# 4_ZynTra-Zynq-PS.net
KiCad netlist of a schematic drawn in Altium Designer
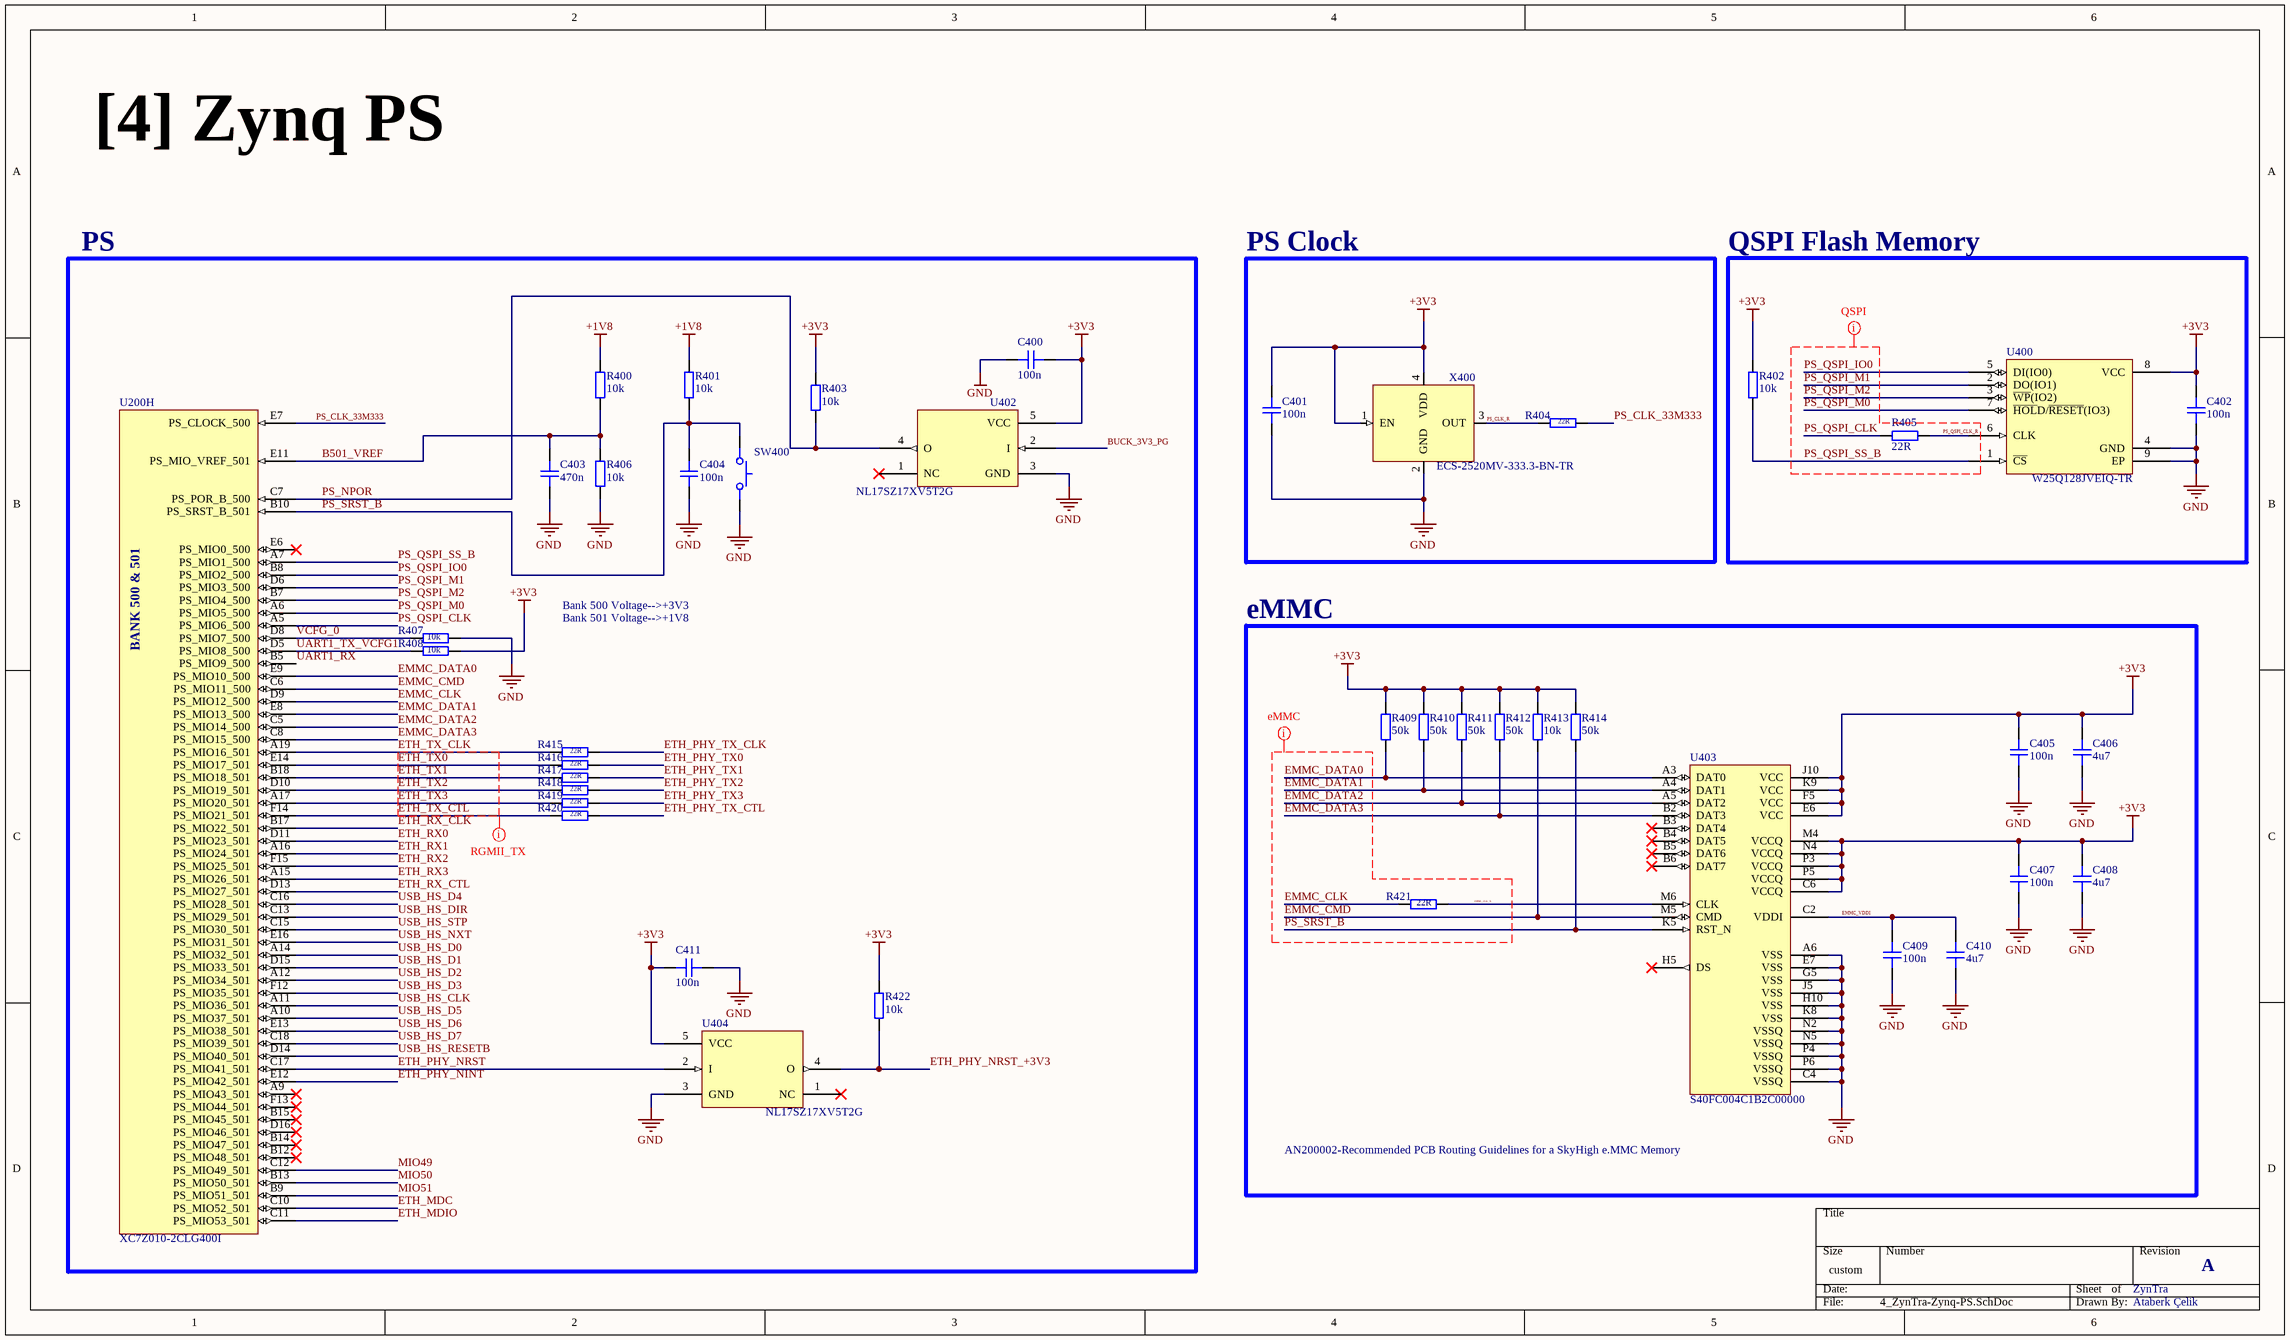
[diagram p0: 4_ZynTra-Zynq-PS.SchDoc]

(export (version "E")
  (design (tool "Eeschema 10.0.6"))
  (components
    (comp (ref "C400")
      (value "100n")
      (footprint "CAP_0201")
      (description "Capacitor SMD 0201")
      (libsource (lib "Schematic-Lib-PhilsLab") (part "CAP_0201"))
    )
    (comp (ref "C401")
      (value "100n")
      (footprint "CAP_0201")
      (description "Capacitor SMD 0201")
      (libsource (lib "Schematic-Lib-PhilsLab") (part "CAP_0201"))
    )
    (comp (ref "C402")
      (value "100n")
      (footprint "CAP_0201")
      (description "Capacitor SMD 0201")
      (libsource (lib "Schematic-Lib-PhilsLab") (part "CAP_0201"))
    )
    (comp (ref "C403")
      (value "470n")
      (footprint "CAP_0201")
      (description "Capacitor SMD 0201")
      (libsource (lib "Schematic-Lib-PhilsLab") (part "CAP_0201"))
    )
    (comp (ref "C404")
      (value "100n")
      (footprint "CAP_0201")
      (description "Capacitor SMD 0201")
      (libsource (lib "Schematic-Lib-PhilsLab") (part "CAP_0201"))
    )
    (comp (ref "C405")
      (value "100n")
      (footprint "CAP_0201")
      (description "Capacitor SMD 0201")
      (libsource (lib "Schematic-Lib-PhilsLab") (part "CAP_0201"))
    )
    (comp (ref "C406")
      (value "4u7")
      (footprint "CAP_0402")
      (description "Capacitor SMD 0402")
      (libsource (lib "Schematic-Lib-PhilsLab") (part "CAP_0402"))
    )
    (comp (ref "C407")
      (value "100n")
      (footprint "CAP_0201")
      (description "Capacitor SMD 0201")
      (libsource (lib "Schematic-Lib-PhilsLab") (part "CAP_0201"))
    )
    (comp (ref "C408")
      (value "4u7")
      (footprint "CAP_0402")
      (description "Capacitor SMD 0402")
      (libsource (lib "Schematic-Lib-PhilsLab") (part "CAP_0402"))
    )
    (comp (ref "C409")
      (value "100n")
      (footprint "CAP_0201")
      (description "Capacitor SMD 0201")
      (libsource (lib "Schematic-Lib-PhilsLab") (part "CAP_0201"))
    )
    (comp (ref "C410")
      (value "4u7")
      (footprint "CAP_0402")
      (description "Capacitor SMD 0402")
      (libsource (lib "Schematic-Lib-PhilsLab") (part "CAP_0402"))
    )
    (comp (ref "C411")
      (value "100n")
      (footprint "CAP_0201")
      (description "Capacitor SMD 0201")
      (libsource (lib "Schematic-Lib-PhilsLab") (part "CAP_0201"))
    )
    (comp (ref "R400")
      (value "10k")
      (footprint "RES_0402")
      (description "Resistor SMD 0402")
      (libsource (lib "Schematic-Lib-PhilsLab") (part "RES_0402"))
    )
    (comp (ref "R401")
      (value "10k")
      (footprint "RES_0402")
      (description "Resistor SMD 0402")
      (libsource (lib "Schematic-Lib-PhilsLab") (part "RES_0402"))
    )
    (comp (ref "R402")
      (value "10k")
      (footprint "RES_0402")
      (description "Resistor SMD 0402")
      (libsource (lib "Schematic-Lib-PhilsLab") (part "RES_0402"))
    )
    (comp (ref "R403")
      (value "10k")
      (footprint "RES_0402")
      (description "Resistor SMD 0402")
      (libsource (lib "Schematic-Lib-PhilsLab") (part "RES_0402"))
    )
    (comp (ref "R404")
      (value "22R")
      (footprint "RES_0402")
      (description "Resistor SMD 0402")
      (libsource (lib "Schematic-Lib-PhilsLab") (part "RES_0402"))
    )
    (comp (ref "R405")
      (value "22R")
      (footprint "RES_0402")
      (description "Resistor SMD 0402")
      (libsource (lib "Schematic-Lib-PhilsLab") (part "RES_0402"))
    )
    (comp (ref "R406")
      (value "10k")
      (footprint "RES_0402")
      (description "Resistor SMD 0402")
      (libsource (lib "Schematic-Lib-PhilsLab") (part "RES_0402"))
    )
    (comp (ref "R407")
      (value "10k")
      (footprint "RES_0402")
      (description "Resistor SMD 0402")
      (libsource (lib "Schematic-Lib-PhilsLab") (part "RES_0402"))
    )
    (comp (ref "R408")
      (value "10k")
      (footprint "RES_0402")
      (description "Resistor SMD 0402")
      (libsource (lib "Schematic-Lib-PhilsLab") (part "RES_0402"))
    )
    (comp (ref "R409")
      (value "50k")
      (footprint "RES_0402")
      (description "Resistor SMD 0402")
      (libsource (lib "Schematic-Lib-PhilsLab") (part "RES_0402"))
    )
    (comp (ref "R410")
      (value "50k")
      (footprint "RES_0402")
      (description "Resistor SMD 0402")
      (libsource (lib "Schematic-Lib-PhilsLab") (part "RES_0402"))
    )
    (comp (ref "R411")
      (value "50k")
      (footprint "RES_0402")
      (description "Resistor SMD 0402")
      (libsource (lib "Schematic-Lib-PhilsLab") (part "RES_0402"))
    )
    (comp (ref "R412")
      (value "50k")
      (footprint "RES_0402")
      (description "Resistor SMD 0402")
      (libsource (lib "Schematic-Lib-PhilsLab") (part "RES_0402"))
    )
    (comp (ref "R413")
      (value "10k")
      (footprint "RES_0402")
      (description "Resistor SMD 0402")
      (libsource (lib "Schematic-Lib-PhilsLab") (part "RES_0402"))
    )
    (comp (ref "R414")
      (value "50k")
      (footprint "RES_0402")
      (description "Resistor SMD 0402")
      (libsource (lib "Schematic-Lib-PhilsLab") (part "RES_0402"))
    )
    (comp (ref "R415")
      (value "22R")
      (footprint "RES_0402")
      (description "Resistor SMD 0402")
      (libsource (lib "Schematic-Lib-PhilsLab") (part "RES_0402"))
    )
    (comp (ref "R416")
      (value "22R")
      (footprint "RES_0402")
      (description "Resistor SMD 0402")
      (libsource (lib "Schematic-Lib-PhilsLab") (part "RES_0402"))
    )
    (comp (ref "R417")
      (value "22R")
      (footprint "RES_0402")
      (description "Resistor SMD 0402")
      (libsource (lib "Schematic-Lib-PhilsLab") (part "RES_0402"))
    )
    (comp (ref "R418")
      (value "22R")
      (footprint "RES_0402")
      (description "Resistor SMD 0402")
      (libsource (lib "Schematic-Lib-PhilsLab") (part "RES_0402"))
    )
    (comp (ref "R419")
      (value "22R")
      (footprint "RES_0402")
      (description "Resistor SMD 0402")
      (libsource (lib "Schematic-Lib-PhilsLab") (part "RES_0402"))
    )
    (comp (ref "R420")
      (value "22R")
      (footprint "RES_0402")
      (description "Resistor SMD 0402")
      (libsource (lib "Schematic-Lib-PhilsLab") (part "RES_0402"))
    )
    (comp (ref "R421")
      (value "22R")
      (footprint "RES_0402")
      (description "Resistor SMD 0402")
      (libsource (lib "Schematic-Lib-PhilsLab") (part "RES_0402"))
    )
    (comp (ref "R422")
      (value "10k")
      (footprint "RES_0402")
      (description "Resistor SMD 0402")
      (libsource (lib "Schematic-Lib-PhilsLab") (part "RES_0402"))
    )
    (comp (ref "SW400")
      (value "SKRPANE010")
      (footprint "SKRPANE010")
      (description "Tactile Switch SMD SPST")
      (fields (field (name "MANUFACTURER") "Alps Alpine"))
      (libsource (lib "Schematic-Lib-PhilsLab") (part "SKRPANE010"))
    )
    (comp (ref "U200")
      (value "XC7Z010-2CLG400I")
      (footprint "CLG400, 0.8mm, 17x17")
      (fields (field (name "MANUFACTURER") "AMD / Xilinx"))
      (libsource (lib "AtaSchLib") (part "XC7Z010-2CLG400I"))
    )
    (comp (ref "U400")
      (value "W25Q128JVEIQ-TR")
      (footprint "WSON8, 8x6mm")
      (description "3V 128M-BIT\r\nSERIAL FLASH MEMORY WITH\r\nDUAL/QUAD SPI")
      (fields
        (field (name "MANUFACTURER") "Winbond")
        (field (name "MANUFACTURER PART NUMBER") "W25Q128JVEIQ TR")
      )
      (libsource (lib "AtaSchLib") (part "W25Q128JVEIQ-TR"))
    )
    (comp (ref "U402")
      (value "NL17SZ17XV5T2G")
      (footprint "SOTFL553, 5 ,1.60x1.20mm")
      (description "Single Non‐Inverting Buffer\r\nwith Schmitt Trigger")
      (fields (field (name "MANUFACTURER") "onsemi"))
      (libsource (lib "") (part "NL17SZ17XV5T2G_1"))
    )
    (comp (ref "U403")
      (value "S40FC004C1B2C00000")
      (footprint "VFBGA-153, 9.00x7.50mm")
      (description "4GB, 3.3 V, e.MMC Flash")
      (fields (field (name "MANUFACTURER") "SkyHigh Memory"))
      (libsource (lib "AtaSchLib") (part "S40FC004C1B2C00000"))
    )
    (comp (ref "U404")
      (value "NL17SZ17XV5T2G")
      (footprint "SOTFL553, 5 ,1.60x1.20mm")
      (description "Single Non‐Inverting Buffer\r\nwith Schmitt Trigger")
      (fields (field (name "MANUFACTURER") "onsemi"))
      (libsource (lib "AtaSchLib") (part "NL17SZ17XV5T2G"))
    )
    (comp (ref "X400")
      (value "ECS-2520MV-333.3-BN-TR")
      (footprint "XTAL_2520")
      (fields
        (field (name "MANUFACTURER") "ECS")
        (field (name "MANUFACTURER PART NUMBER") "ECS-2520MV-130-BN-TR")
      )
      (libsource (lib "Schematic-Lib-PhilsLab") (part "ECS-2520MV-130-BN-TR"))
    )
  )
  (nets
    (net (code "1") (name "+1V8") (class "Default")
      (node (ref "R400") (pin "1") (pinfunction "1_1") (pintype "passive"))
      (node (ref "R401") (pin "1") (pinfunction "1_1") (pintype "passive"))
    )
    (net (code "2") (name "+3V3") (class "Default")
      (node (ref "C400") (pin "1") (pinfunction "1_1") (pintype "passive"))
      (node (ref "C401") (pin "2") (pinfunction "2_2") (pintype "passive"))
      (node (ref "C402") (pin "1") (pinfunction "1_1") (pintype "passive"))
      (node (ref "C405") (pin "2") (pinfunction "2_2") (pintype "passive"))
      (node (ref "C406") (pin "2") (pinfunction "2_2") (pintype "passive"))
      (node (ref "C407") (pin "2") (pinfunction "2_2") (pintype "passive"))
      (node (ref "C408") (pin "2") (pinfunction "2_2") (pintype "passive"))
      (node (ref "C411") (pin "2") (pinfunction "2_2") (pintype "passive"))
      (node (ref "R402") (pin "1") (pinfunction "1_1") (pintype "passive"))
      (node (ref "R403") (pin "1") (pinfunction "1_1") (pintype "passive"))
      (node (ref "R408") (pin "2") (pinfunction "2_2") (pintype "passive"))
      (node (ref "R409") (pin "1") (pinfunction "1_1") (pintype "passive"))
      (node (ref "R410") (pin "1") (pinfunction "1_1") (pintype "passive"))
      (node (ref "R411") (pin "1") (pinfunction "1_1") (pintype "passive"))
      (node (ref "R412") (pin "1") (pinfunction "1_1") (pintype "passive"))
      (node (ref "R413") (pin "1") (pinfunction "1_1") (pintype "passive"))
      (node (ref "R414") (pin "1") (pinfunction "1_1") (pintype "passive"))
      (node (ref "R422") (pin "1") (pinfunction "1_1") (pintype "passive"))
      (node (ref "U400") (pin "8") (pinfunction "VCC_8") (pintype "power_in"))
      (node (ref "U402") (pin "5") (pinfunction "VCC_5") (pintype "power_in"))
      (node (ref "U403") (pin "C6") (pinfunction "VCCQ_C6") (pintype "power_in"))
      (node (ref "U403") (pin "E6") (pinfunction "VCC_E6") (pintype "power_in"))
      (node (ref "U403") (pin "F5") (pinfunction "VCC_F5") (pintype "power_in"))
      (node (ref "U403") (pin "J10") (pinfunction "VCC_J10") (pintype "power_in"))
      (node (ref "U403") (pin "K9") (pinfunction "VCC_K9") (pintype "power_in"))
      (node (ref "U403") (pin "M4") (pinfunction "VCCQ_M4") (pintype "power_in"))
      (node (ref "U403") (pin "N4") (pinfunction "VCCQ_N4") (pintype "power_in"))
      (node (ref "U403") (pin "P3") (pinfunction "VCCQ_P3") (pintype "power_in"))
      (node (ref "U403") (pin "P5") (pinfunction "VCCQ_P5") (pintype "power_in"))
      (node (ref "U404") (pin "5") (pinfunction "VCC_5") (pintype "power_in"))
      (node (ref "X400") (pin "1") (pinfunction "EN_1") (pintype "input"))
      (node (ref "X400") (pin "4") (pinfunction "VDD_4") (pintype "power_in"))
    )
    (net (code "3") (name "/B501_VREF") (class "Default")
      (node (ref "C403") (pin "2") (pinfunction "2_2") (pintype "passive"))
      (node (ref "R400") (pin "2") (pinfunction "2_2") (pintype "passive"))
      (node (ref "R406") (pin "1") (pinfunction "1_1") (pintype "passive"))
      (node (ref "U200") (pin "E11") (pinfunction "PS_MIO_VREF_501_E11") (pintype "input"))
    )
    (net (code "4") (name "/BUCK_3V3_PG") (class "Default")
      (node (ref "U402") (pin "2") (pinfunction "I_2") (pintype "input"))
    )
    (net (code "5") (name "/EMMC_CLK") (class "Default")
      (node (ref "R421") (pin "2") (pinfunction "2_2") (pintype "passive"))
      (node (ref "U200") (pin "D9") (pinfunction "PS_MIO12_500_D9") (pintype "bidirectional"))
    )
    (net (code "6") (name "/EMMC_CLK_R") (class "Default")
      (node (ref "R421") (pin "1") (pinfunction "1_1") (pintype "passive"))
      (node (ref "U403") (pin "M6") (pinfunction "CLK_M6") (pintype "input"))
    )
    (net (code "7") (name "/EMMC_CMD") (class "Default")
      (node (ref "R413") (pin "2") (pinfunction "2_2") (pintype "passive"))
      (node (ref "U200") (pin "C6") (pinfunction "PS_MIO11_500_C6") (pintype "bidirectional"))
      (node (ref "U403") (pin "M5") (pinfunction "CMD_M5") (pintype "bidirectional"))
    )
    (net (code "8") (name "/EMMC_DATA0") (class "Default")
      (node (ref "R409") (pin "2") (pinfunction "2_2") (pintype "passive"))
      (node (ref "U200") (pin "E9") (pinfunction "PS_MIO10_500_E9") (pintype "bidirectional"))
      (node (ref "U403") (pin "A3") (pinfunction "DAT0_A3") (pintype "bidirectional"))
    )
    (net (code "9") (name "/EMMC_DATA1") (class "Default")
      (node (ref "R410") (pin "2") (pinfunction "2_2") (pintype "passive"))
      (node (ref "U200") (pin "E8") (pinfunction "PS_MIO13_500_E8") (pintype "bidirectional"))
      (node (ref "U403") (pin "A4") (pinfunction "DAT1_A4") (pintype "bidirectional"))
    )
    (net (code "10") (name "/EMMC_DATA2") (class "Default")
      (node (ref "R411") (pin "2") (pinfunction "2_2") (pintype "passive"))
      (node (ref "U200") (pin "C5") (pinfunction "PS_MIO14_500_C5") (pintype "bidirectional"))
      (node (ref "U403") (pin "A5") (pinfunction "DAT2_A5") (pintype "bidirectional"))
    )
    (net (code "11") (name "/EMMC_DATA3") (class "Default")
      (node (ref "R412") (pin "2") (pinfunction "2_2") (pintype "passive"))
      (node (ref "U200") (pin "C8") (pinfunction "PS_MIO15_500_C8") (pintype "bidirectional"))
      (node (ref "U403") (pin "B2") (pinfunction "DAT3_B2") (pintype "bidirectional"))
    )
    (net (code "12") (name "/EMMC_VDDI") (class "Default")
      (node (ref "C409") (pin "2") (pinfunction "2_2") (pintype "passive"))
      (node (ref "C410") (pin "2") (pinfunction "2_2") (pintype "passive"))
      (node (ref "U403") (pin "C2") (pinfunction "VDDI_C2") (pintype "power_in"))
    )
    (net (code "13") (name "/ETH_MDC") (class "Default")
      (node (ref "U200") (pin "C10") (pinfunction "PS_MIO52_501_C10") (pintype "bidirectional"))
    )
    (net (code "14") (name "/ETH_MDIO") (class "Default")
      (node (ref "U200") (pin "C11") (pinfunction "PS_MIO53_501_C11") (pintype "bidirectional"))
    )
    (net (code "15") (name "/ETH_PHY_NINT") (class "Default")
      (node (ref "U200") (pin "E12") (pinfunction "PS_MIO42_501_E12") (pintype "bidirectional"))
    )
    (net (code "16") (name "/ETH_PHY_NRST") (class "Default")
      (node (ref "U200") (pin "C17") (pinfunction "PS_MIO41_501_C17") (pintype "bidirectional"))
      (node (ref "U404") (pin "2") (pinfunction "I_2") (pintype "input"))
    )
    (net (code "17") (name "/ETH_PHY_NRST_+3V3") (class "Default")
      (node (ref "R422") (pin "2") (pinfunction "2_2") (pintype "passive"))
      (node (ref "U404") (pin "4") (pinfunction "O_4") (pintype "output"))
    )
    (net (code "18") (name "/ETH_PHY_TX0") (class "Default")
      (node (ref "R416") (pin "1") (pinfunction "1_1") (pintype "passive"))
    )
    (net (code "19") (name "/ETH_PHY_TX1") (class "Default")
      (node (ref "R417") (pin "1") (pinfunction "1_1") (pintype "passive"))
    )
    (net (code "20") (name "/ETH_PHY_TX2") (class "Default")
      (node (ref "R418") (pin "1") (pinfunction "1_1") (pintype "passive"))
    )
    (net (code "21") (name "/ETH_PHY_TX3") (class "Default")
      (node (ref "R419") (pin "1") (pinfunction "1_1") (pintype "passive"))
    )
    (net (code "22") (name "/ETH_PHY_TX_CLK") (class "Default")
      (node (ref "R415") (pin "1") (pinfunction "1_1") (pintype "passive"))
    )
    (net (code "23") (name "/ETH_PHY_TX_CTL") (class "Default")
      (node (ref "R420") (pin "1") (pinfunction "1_1") (pintype "passive"))
    )
    (net (code "24") (name "/ETH_RX0") (class "Default")
      (node (ref "U200") (pin "D11") (pinfunction "PS_MIO23_501_D11") (pintype "bidirectional"))
    )
    (net (code "25") (name "/ETH_RX1") (class "Default")
      (node (ref "U200") (pin "A16") (pinfunction "PS_MIO24_501_A16") (pintype "bidirectional"))
    )
    (net (code "26") (name "/ETH_RX2") (class "Default")
      (node (ref "U200") (pin "F15") (pinfunction "PS_MIO25_501_F15") (pintype "bidirectional"))
    )
    (net (code "27") (name "/ETH_RX3") (class "Default")
      (node (ref "U200") (pin "A15") (pinfunction "PS_MIO26_501_A15") (pintype "bidirectional"))
    )
    (net (code "28") (name "/ETH_RX_CLK") (class "Default")
      (node (ref "U200") (pin "B17") (pinfunction "PS_MIO22_501_B17") (pintype "bidirectional"))
    )
    (net (code "29") (name "/ETH_RX_CTL") (class "Default")
      (node (ref "U200") (pin "D13") (pinfunction "PS_MIO27_501_D13") (pintype "bidirectional"))
    )
    (net (code "30") (name "/ETH_TX0") (class "Default")
      (node (ref "R416") (pin "2") (pinfunction "2_2") (pintype "passive"))
      (node (ref "U200") (pin "E14") (pinfunction "PS_MIO17_501_E14") (pintype "bidirectional"))
    )
    (net (code "31") (name "/ETH_TX1") (class "Default")
      (node (ref "R417") (pin "2") (pinfunction "2_2") (pintype "passive"))
      (node (ref "U200") (pin "B18") (pinfunction "PS_MIO18_501_B18") (pintype "bidirectional"))
    )
    (net (code "32") (name "/ETH_TX2") (class "Default")
      (node (ref "R418") (pin "2") (pinfunction "2_2") (pintype "passive"))
      (node (ref "U200") (pin "D10") (pinfunction "PS_MIO19_501_D10") (pintype "bidirectional"))
    )
    (net (code "33") (name "/ETH_TX3") (class "Default")
      (node (ref "R419") (pin "2") (pinfunction "2_2") (pintype "passive"))
      (node (ref "U200") (pin "A17") (pinfunction "PS_MIO20_501_A17") (pintype "bidirectional"))
    )
    (net (code "34") (name "/ETH_TX_CLK") (class "Default")
      (node (ref "R415") (pin "2") (pinfunction "2_2") (pintype "passive"))
      (node (ref "U200") (pin "A19") (pinfunction "PS_MIO16_501_A19") (pintype "bidirectional"))
    )
    (net (code "35") (name "/ETH_TX_CTL") (class "Default")
      (node (ref "R420") (pin "2") (pinfunction "2_2") (pintype "passive"))
      (node (ref "U200") (pin "F14") (pinfunction "PS_MIO21_501_F14") (pintype "bidirectional"))
    )
    (net (code "36") (name "/MIO49") (class "Default")
      (node (ref "U200") (pin "C12") (pinfunction "PS_MIO49_501_C12") (pintype "bidirectional"))
    )
    (net (code "37") (name "/MIO50") (class "Default")
      (node (ref "U200") (pin "B13") (pinfunction "PS_MIO50_501_B13") (pintype "bidirectional"))
    )
    (net (code "38") (name "/MIO51") (class "Default")
      (node (ref "U200") (pin "B9") (pinfunction "PS_MIO51_501_B9") (pintype "bidirectional"))
    )
    (net (code "39") (name "/PS_CLK_33M333") (class "Default")
      (node (ref "R404") (pin "1") (pinfunction "1_1") (pintype "passive"))
      (node (ref "U200") (pin "E7") (pinfunction "PS_CLOCK_500_E7") (pintype "input"))
    )
    (net (code "40") (name "/PS_CLK_R") (class "Default")
      (node (ref "R404") (pin "2") (pinfunction "2_2") (pintype "passive"))
      (node (ref "X400") (pin "3") (pinfunction "OUT_3") (pintype "passive"))
    )
    (net (code "41") (name "/PS_NPOR") (class "Default")
      (node (ref "R403") (pin "2") (pinfunction "2_2") (pintype "passive"))
      (node (ref "U200") (pin "C7") (pinfunction "PS_POR_B_500_C7") (pintype "input"))
      (node (ref "U402") (pin "4") (pinfunction "O_4") (pintype "output"))
    )
    (net (code "42") (name "/PS_QSPI_CLK") (class "Default")
      (node (ref "R405") (pin "2") (pinfunction "2_2") (pintype "passive"))
      (node (ref "U200") (pin "A5") (pinfunction "PS_MIO6_500_A5") (pintype "bidirectional"))
    )
    (net (code "43") (name "/PS_QSPI_CLK_R") (class "Default")
      (node (ref "R405") (pin "1") (pinfunction "1_1") (pintype "passive"))
      (node (ref "U400") (pin "6") (pinfunction "CLK_6") (pintype "input"))
    )
    (net (code "44") (name "/PS_QSPI_IO0") (class "Default")
      (node (ref "U200") (pin "B8") (pinfunction "PS_MIO2_500_B8") (pintype "bidirectional"))
      (node (ref "U400") (pin "5") (pinfunction "DI(IO0)_5") (pintype "bidirectional"))
    )
    (net (code "45") (name "/PS_QSPI_M0") (class "Default")
      (node (ref "U200") (pin "A6") (pinfunction "PS_MIO5_500_A6") (pintype "bidirectional"))
      (node (ref "U400") (pin "7") (pinfunction "~{HOL}D/~{RESET}(IO3)_7") (pintype "bidirectional"))
    )
    (net (code "46") (name "/PS_QSPI_M1") (class "Default")
      (node (ref "U200") (pin "D6") (pinfunction "PS_MIO3_500_D6") (pintype "bidirectional"))
      (node (ref "U400") (pin "2") (pinfunction "DO(IO1)_2") (pintype "bidirectional"))
    )
    (net (code "47") (name "/PS_QSPI_M2") (class "Default")
      (node (ref "U200") (pin "B7") (pinfunction "PS_MIO4_500_B7") (pintype "bidirectional"))
      (node (ref "U400") (pin "3") (pinfunction "~{WP}(IO2)_3") (pintype "bidirectional"))
    )
    (net (code "48") (name "/PS_QSPI_SS_B") (class "Default")
      (node (ref "R402") (pin "2") (pinfunction "2_2") (pintype "passive"))
      (node (ref "U200") (pin "A7") (pinfunction "PS_MIO1_500_A7") (pintype "bidirectional"))
      (node (ref "U400") (pin "1") (pinfunction "~{CS}_1") (pintype "input"))
    )
    (net (code "49") (name "/PS_SRST_B") (class "Default")
      (node (ref "C404") (pin "2") (pinfunction "2_2") (pintype "passive"))
      (node (ref "R401") (pin "2") (pinfunction "2_2") (pintype "passive"))
      (node (ref "R414") (pin "2") (pinfunction "2_2") (pintype "passive"))
      (node (ref "SW400") (pin "12") (pintype "passive"))
      (node (ref "U200") (pin "B10") (pinfunction "PS_SRST_B_501_B10") (pintype "input"))
      (node (ref "U403") (pin "K5") (pinfunction "RST_N_K5") (pintype "input"))
    )
    (net (code "50") (name "/UART1_RX") (class "Default")
      (node (ref "U200") (pin "B5") (pinfunction "PS_MIO9_500_B5") (pintype "bidirectional"))
    )
    (net (code "51") (name "/UART1_TX_VCFG1") (class "Default")
      (node (ref "R408") (pin "1") (pinfunction "1_1") (pintype "passive"))
      (node (ref "U200") (pin "D5") (pinfunction "PS_MIO8_500_D5") (pintype "bidirectional"))
    )
    (net (code "52") (name "/USB_HS_CLK") (class "Default")
      (node (ref "U200") (pin "A11") (pinfunction "PS_MIO36_501_A11") (pintype "bidirectional"))
    )
    (net (code "53") (name "/USB_HS_D0") (class "Default")
      (node (ref "U200") (pin "A14") (pinfunction "PS_MIO32_501_A14") (pintype "bidirectional"))
    )
    (net (code "54") (name "/USB_HS_D1") (class "Default")
      (node (ref "U200") (pin "D15") (pinfunction "PS_MIO33_501_D15") (pintype "bidirectional"))
    )
    (net (code "55") (name "/USB_HS_D2") (class "Default")
      (node (ref "U200") (pin "A12") (pinfunction "PS_MIO34_501_A12") (pintype "bidirectional"))
    )
    (net (code "56") (name "/USB_HS_D3") (class "Default")
      (node (ref "U200") (pin "F12") (pinfunction "PS_MIO35_501_F12") (pintype "bidirectional"))
    )
    (net (code "57") (name "/USB_HS_D4") (class "Default")
      (node (ref "U200") (pin "C16") (pinfunction "PS_MIO28_501_C16") (pintype "bidirectional"))
    )
    (net (code "58") (name "/USB_HS_D5") (class "Default")
      (node (ref "U200") (pin "A10") (pinfunction "PS_MIO37_501_A10") (pintype "bidirectional"))
    )
    (net (code "59") (name "/USB_HS_D6") (class "Default")
      (node (ref "U200") (pin "E13") (pinfunction "PS_MIO38_501_E13") (pintype "bidirectional"))
    )
    (net (code "60") (name "/USB_HS_D7") (class "Default")
      (node (ref "U200") (pin "C18") (pinfunction "PS_MIO39_501_C18") (pintype "bidirectional"))
    )
    (net (code "61") (name "/USB_HS_DIR") (class "Default")
      (node (ref "U200") (pin "C13") (pinfunction "PS_MIO29_501_C13") (pintype "bidirectional"))
    )
    (net (code "62") (name "/USB_HS_NXT") (class "Default")
      (node (ref "U200") (pin "E16") (pinfunction "PS_MIO31_501_E16") (pintype "bidirectional"))
    )
    (net (code "63") (name "/USB_HS_RESETB") (class "Default")
      (node (ref "U200") (pin "D14") (pinfunction "PS_MIO40_501_D14") (pintype "bidirectional"))
    )
    (net (code "64") (name "/USB_HS_STP") (class "Default")
      (node (ref "U200") (pin "C15") (pinfunction "PS_MIO30_501_C15") (pintype "bidirectional"))
    )
    (net (code "65") (name "/VCFG_0") (class "Default")
      (node (ref "R407") (pin "1") (pinfunction "1_1") (pintype "passive"))
      (node (ref "U200") (pin "D8") (pinfunction "PS_MIO7_500_D8") (pintype "bidirectional"))
    )
    (net (code "66") (name "GND") (class "Default")
      (node (ref "C400") (pin "2") (pinfunction "2_2") (pintype "passive"))
      (node (ref "C401") (pin "1") (pinfunction "1_1") (pintype "passive"))
      (node (ref "C402") (pin "2") (pinfunction "2_2") (pintype "passive"))
      (node (ref "C403") (pin "1") (pinfunction "1_1") (pintype "passive"))
      (node (ref "C404") (pin "1") (pinfunction "1_1") (pintype "passive"))
      (node (ref "C405") (pin "1") (pinfunction "1_1") (pintype "passive"))
      (node (ref "C406") (pin "1") (pinfunction "1_1") (pintype "passive"))
      (node (ref "C407") (pin "1") (pinfunction "1_1") (pintype "passive"))
      (node (ref "C408") (pin "1") (pinfunction "1_1") (pintype "passive"))
      (node (ref "C409") (pin "1") (pinfunction "1_1") (pintype "passive"))
      (node (ref "C410") (pin "1") (pinfunction "1_1") (pintype "passive"))
      (node (ref "C411") (pin "1") (pinfunction "1_1") (pintype "passive"))
      (node (ref "R406") (pin "2") (pinfunction "2_2") (pintype "passive"))
      (node (ref "R407") (pin "2") (pinfunction "2_2") (pintype "passive"))
      (node (ref "SW400") (pin "34") (pintype "passive"))
      (node (ref "U400") (pin "4") (pinfunction "GND_4") (pintype "power_in"))
      (node (ref "U400") (pin "9") (pinfunction "EP_9") (pintype "power_in"))
      (node (ref "U402") (pin "3") (pinfunction "GND_3") (pintype "power_in"))
      (node (ref "U403") (pin "A6") (pinfunction "VSS_A6") (pintype "power_in"))
      (node (ref "U403") (pin "C4") (pinfunction "VSSQ_C4") (pintype "power_in"))
      (node (ref "U403") (pin "E7") (pinfunction "VSS_E7") (pintype "power_in"))
      (node (ref "U403") (pin "G5") (pinfunction "VSS_G5") (pintype "power_in"))
      (node (ref "U403") (pin "H10") (pinfunction "VSS_H10") (pintype "power_in"))
      (node (ref "U403") (pin "J5") (pinfunction "VSS_J5") (pintype "power_in"))
      (node (ref "U403") (pin "K8") (pinfunction "VSS_K8") (pintype "power_in"))
      (node (ref "U403") (pin "N2") (pinfunction "VSSQ_N2") (pintype "power_in"))
      (node (ref "U403") (pin "N5") (pinfunction "VSSQ_N5") (pintype "power_in"))
      (node (ref "U403") (pin "P4") (pinfunction "VSSQ_P4") (pintype "power_in"))
      (node (ref "U403") (pin "P6") (pinfunction "VSSQ_P6") (pintype "power_in"))
      (node (ref "U404") (pin "3") (pinfunction "GND_3") (pintype "power_in"))
      (node (ref "X400") (pin "2") (pinfunction "GND_2") (pintype "power_in"))
    )
    (net (code "67") (name "unconnected-(U200H-PS_MIO0_500-PadE6)") (class "Default")
      (node (ref "U200") (pin "E6") (pinfunction "PS_MIO0_500_E6") (pintype "bidirectional+no_connect"))
    )
    (net (code "68") (name "unconnected-(U200H-PS_MIO43_501-PadA9)") (class "Default")
      (node (ref "U200") (pin "A9") (pinfunction "PS_MIO43_501_A9") (pintype "bidirectional+no_connect"))
    )
    (net (code "69") (name "unconnected-(U200H-PS_MIO44_501-PadF13)") (class "Default")
      (node (ref "U200") (pin "F13") (pinfunction "PS_MIO44_501_F13") (pintype "bidirectional+no_connect"))
    )
    (net (code "70") (name "unconnected-(U200H-PS_MIO45_501-PadB15)") (class "Default")
      (node (ref "U200") (pin "B15") (pinfunction "PS_MIO45_501_B15") (pintype "bidirectional+no_connect"))
    )
    (net (code "71") (name "unconnected-(U200H-PS_MIO46_501-PadD16)") (class "Default")
      (node (ref "U200") (pin "D16") (pinfunction "PS_MIO46_501_D16") (pintype "bidirectional+no_connect"))
    )
    (net (code "72") (name "unconnected-(U200H-PS_MIO47_501-PadB14)") (class "Default")
      (node (ref "U200") (pin "B14") (pinfunction "PS_MIO47_501_B14") (pintype "bidirectional+no_connect"))
    )
    (net (code "73") (name "unconnected-(U200H-PS_MIO48_501-PadB12)") (class "Default")
      (node (ref "U200") (pin "B12") (pinfunction "PS_MIO48_501_B12") (pintype "bidirectional+no_connect"))
    )
    (net (code "74") (name "unconnected-(U402-NC-Pad1)") (class "Default")
      (node (ref "U402") (pin "1") (pinfunction "NC_1") (pintype "passive+no_connect"))
    )
    (net (code "75") (name "unconnected-(U403-DAT4-PadB3)") (class "Default")
      (node (ref "U403") (pin "B3") (pinfunction "DAT4_B3") (pintype "bidirectional+no_connect"))
    )
    (net (code "76") (name "unconnected-(U403-DAT5-PadB4)") (class "Default")
      (node (ref "U403") (pin "B4") (pinfunction "DAT5_B4") (pintype "bidirectional+no_connect"))
    )
    (net (code "77") (name "unconnected-(U403-DAT6-PadB5)") (class "Default")
      (node (ref "U403") (pin "B5") (pinfunction "DAT6_B5") (pintype "bidirectional+no_connect"))
    )
    (net (code "78") (name "unconnected-(U403-DAT7-PadB6)") (class "Default")
      (node (ref "U403") (pin "B6") (pinfunction "DAT7_B6") (pintype "bidirectional+no_connect"))
    )
    (net (code "79") (name "unconnected-(U403-DS-PadH5)") (class "Default")
      (node (ref "U403") (pin "H5") (pinfunction "DS_H5") (pintype "output+no_connect"))
    )
    (net (code "80") (name "unconnected-(U404-NC-Pad1)") (class "Default")
      (node (ref "U404") (pin "1") (pinfunction "NC_1") (pintype "passive+no_connect"))
    )
  )
)
